# SparkFun_Venus_GPS_SMA_Connector.net
KiCad netlist of a schematic drawn in EAGLE
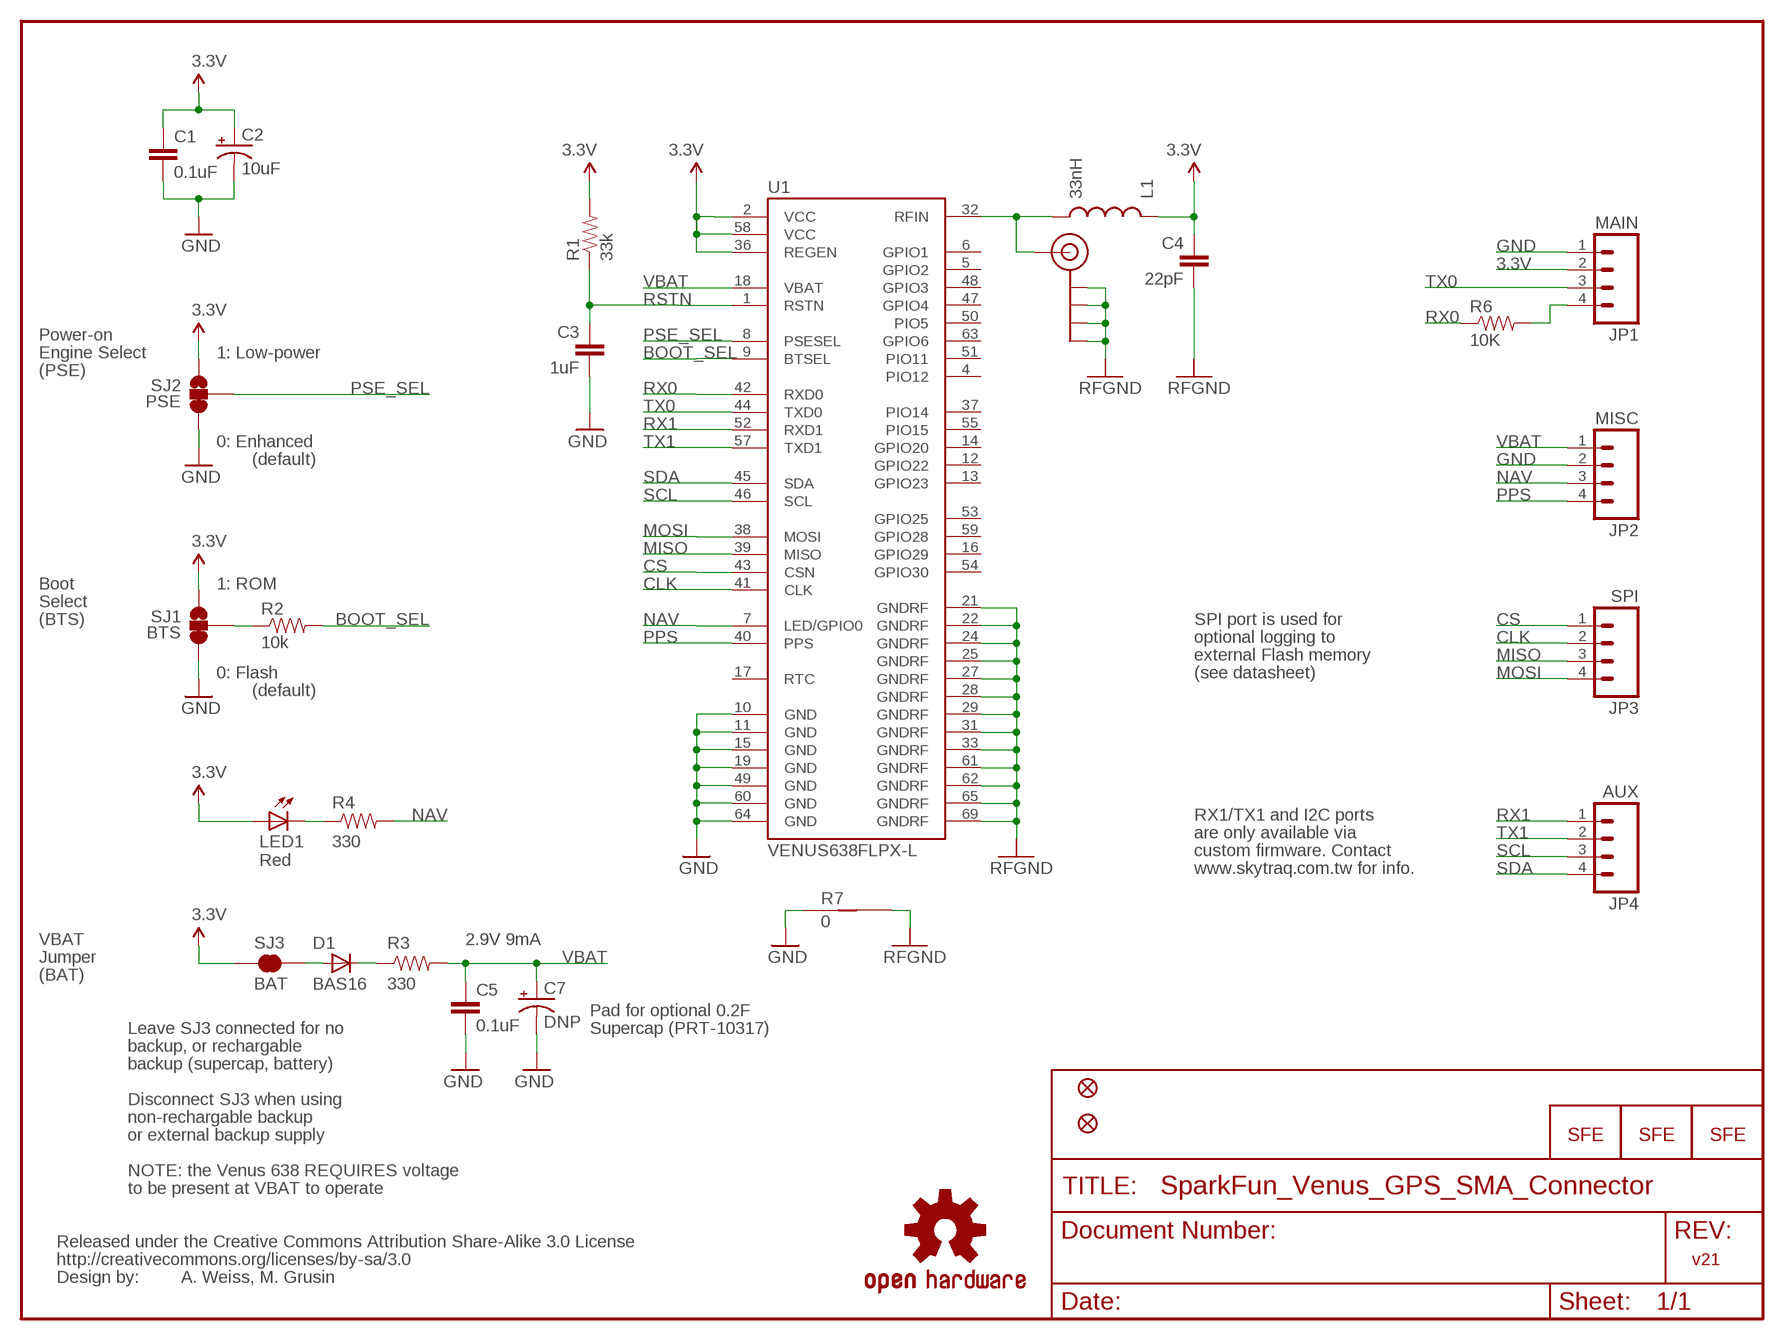
[diagram p0: schematic, sheet 1]

(export (version "E")
  (design (tool "Eeschema 10.0.6"))
  (components
    (comp (ref "C1")
      (value "0.1uF")
      (footprint "eagle-import:0402-CAP")
      (libsource (lib "eagle-import") (part "CAP0402-CAP"))
    )
    (comp (ref "C2")
      (value "10uF")
      (footprint "eagle-import:EIA3216")
      (libsource (lib "eagle-import") (part "CAP_POL1206"))
    )
    (comp (ref "C3")
      (value "1uF")
      (footprint "eagle-import:0402-CAP")
      (libsource (lib "eagle-import") (part "CAP0402-CAP"))
    )
    (comp (ref "C4")
      (value "22pF")
      (footprint "eagle-import:0402-CAP")
      (libsource (lib "eagle-import") (part "CAP0402-CAP"))
    )
    (comp (ref "C5")
      (value "0.1uF")
      (footprint "eagle-import:0402-CAP")
      (libsource (lib "eagle-import") (part "CAP0402-CAP"))
    )
    (comp (ref "C7")
      (value "DNP")
      (footprint "eagle-import:EN_J2")
      (libsource (lib "eagle-import") (part "CAP_POLEN_J2"))
    )
    (comp (ref "D1")
      (value "BAS16")
      (footprint "eagle-import:SOD-323")
      (libsource (lib "eagle-import") (part "DIODESOD"))
    )
    (comp (ref "JP1")
      (value "MAIN")
      (footprint "eagle-import:1X04")
      (libsource (lib "eagle-import") (part "M04PTH"))
    )
    (comp (ref "JP2")
      (value "MISC")
      (footprint "eagle-import:1X04")
      (libsource (lib "eagle-import") (part "M04PTH"))
    )
    (comp (ref "JP3")
      (value "SPI")
      (footprint "eagle-import:1X04")
      (libsource (lib "eagle-import") (part "M04PTH"))
    )
    (comp (ref "JP4")
      (value "AUX")
      (footprint "eagle-import:1X04")
      (libsource (lib "eagle-import") (part "M04PTH"))
    )
    (comp (ref "JP5")
      (value "SMA_EDGE")
      (footprint "eagle-import:SMA-EDGE")
      (libsource (lib "eagle-import") (part "SMA_EDGE"))
    )
    (comp (ref "JP6")
      (value "FIDUCIALUFIDUCIAL")
      (footprint "eagle-import:MICRO-FIDUCIAL")
      (libsource (lib "eagle-import") (part "FIDUCIALUFIDUCIAL"))
    )
    (comp (ref "JP7")
      (value "FIDUCIALUFIDUCIAL")
      (footprint "eagle-import:MICRO-FIDUCIAL")
      (libsource (lib "eagle-import") (part "FIDUCIALUFIDUCIAL"))
    )
    (comp (ref "L1")
      (value "33nH")
      (footprint "eagle-import:C0402")
      (libsource (lib "eagle-import") (part "INDUCTOR0402"))
    )
    (comp (ref "LED1")
      (value "Red")
      (footprint "eagle-import:LED-0603")
      (libsource (lib "eagle-import") (part "LED0603"))
    )
    (comp (ref "LOGO1")
      (value "LOGO-SFESK")
      (footprint "eagle-import:SFE-LOGO-FLAME")
      (libsource (lib "eagle-import") (part "LOGO-SFESK"))
    )
    (comp (ref "LOGO2")
      (value "LOGO-SFESK")
      (footprint "eagle-import:SFE-LOGO-FLAME")
      (libsource (lib "eagle-import") (part "LOGO-SFESK"))
    )
    (comp (ref "LOGO3")
      (value "LOGO-SFENW2")
      (footprint "eagle-import:SFE-NEW-WEB")
      (libsource (lib "eagle-import") (part "LOGO-SFENW2"))
    )
    (comp (ref "R1")
      (value "33k")
      (footprint "eagle-import:0402-RES")
      (libsource (lib "eagle-import") (part "RESISTOR0402-RES"))
    )
    (comp (ref "R2")
      (value "10k")
      (footprint "eagle-import:0402-RES")
      (libsource (lib "eagle-import") (part "RESISTOR0402-RES"))
    )
    (comp (ref "R3")
      (value "330")
      (footprint "eagle-import:0402-RES")
      (libsource (lib "eagle-import") (part "RESISTOR0402-RES"))
    )
    (comp (ref "R4")
      (value "330")
      (footprint "eagle-import:0402-RES")
      (libsource (lib "eagle-import") (part "RESISTOR0402-RES"))
    )
    (comp (ref "R6")
      (value "10K")
      (footprint "eagle-import:0402-RES")
      (libsource (lib "eagle-import") (part "RESISTOR0402-RES"))
    )
    (comp (ref "R7")
      (value "0")
      (footprint "eagle-import:GND-JUMP")
      (libsource (lib "eagle-import") (part "GND-JUMP"))
    )
    (comp (ref "SJ1")
      (value "BTS")
      (footprint "eagle-import:SJ_3_PASTE2&3")
      (libsource (lib "eagle-import") (part "SOLDERJUMPER_2WAYPASTE2&3"))
    )
    (comp (ref "SJ2")
      (value "PSE")
      (footprint "eagle-import:SJ_3_PASTE2&3")
      (libsource (lib "eagle-import") (part "SOLDERJUMPER_2WAYPASTE2&3"))
    )
    (comp (ref "SJ3")
      (value "BAT")
      (footprint "eagle-import:SJ_2S")
      (libsource (lib "eagle-import") (part "SOLDERJUMPERNC"))
    )
    (comp (ref "U$4")
      (value "OSHW-LOGOS")
      (footprint "eagle-import:OSHW-LOGO-S")
      (libsource (lib "eagle-import") (part "OSHW-LOGOS"))
    )
    (comp (ref "U$5")
      (value "CREATIVE_COMMONS")
      (footprint "eagle-import:CREATIVE_COMMONS")
      (libsource (lib "eagle-import") (part "CREATIVE_COMMONS"))
    )
    (comp (ref "U1")
      (value "VENUS638FLPX-L")
      (footprint "eagle-import:VENUS638FLPX")
      (libsource (lib "eagle-import") (part "VENUS638FLPX-L"))
    )
  )
  (nets
    (net (code "1") (name "/BOOT_SEL") (class "Default")
      (node (ref "R2") (pin "2") (pinfunction "2_2") (pintype "passive"))
      (node (ref "U1") (pin "9") (pinfunction "BTSEL_9") (pintype "bidirectional"))
    )
    (net (code "2") (name "/CLK") (class "Default")
      (node (ref "JP3") (pin "2") (pinfunction "2_2") (pintype "passive"))
      (node (ref "U1") (pin "41") (pinfunction "CLK_41") (pintype "bidirectional"))
    )
    (net (code "3") (name "/CS") (class "Default")
      (node (ref "JP3") (pin "1") (pinfunction "1_1") (pintype "passive"))
      (node (ref "U1") (pin "43") (pinfunction "CSN_43") (pintype "bidirectional"))
    )
    (net (code "4") (name "/MISO") (class "Default")
      (node (ref "JP3") (pin "3") (pinfunction "3_3") (pintype "passive"))
      (node (ref "U1") (pin "39") (pinfunction "MISO_39") (pintype "bidirectional"))
    )
    (net (code "5") (name "/MOSI") (class "Default")
      (node (ref "JP3") (pin "4") (pinfunction "4_4") (pintype "passive"))
      (node (ref "U1") (pin "38") (pinfunction "MOSI_38") (pintype "bidirectional"))
    )
    (net (code "6") (name "/NAV") (class "Default")
      (node (ref "JP2") (pin "3") (pinfunction "3_3") (pintype "passive"))
      (node (ref "R4") (pin "2") (pinfunction "2_2") (pintype "passive"))
      (node (ref "U1") (pin "7") (pinfunction "LED/GPIO0_7") (pintype "bidirectional"))
    )
    (net (code "7") (name "/PPS") (class "Default")
      (node (ref "JP2") (pin "4") (pinfunction "4_4") (pintype "passive"))
      (node (ref "U1") (pin "40") (pinfunction "PPS_40") (pintype "bidirectional"))
    )
    (net (code "8") (name "/PSE_SEL") (class "Default")
      (node (ref "SJ2") (pin "2") (pinfunction "2_2") (pintype "passive"))
      (node (ref "U1") (pin "8") (pinfunction "PSESEL_8") (pintype "bidirectional"))
    )
    (net (code "9") (name "/RFGND") (class "Default")
      (node (ref "C4") (pin "2") (pinfunction "2_2") (pintype "passive"))
      (node (ref "JP5") (pin "GND@0") (pinfunction "GND_GND@0") (pintype "bidirectional"))
      (node (ref "JP5") (pin "GND@1") (pinfunction "GND_GND@1") (pintype "bidirectional"))
      (node (ref "JP5") (pin "GND@2") (pinfunction "GND_GND@2") (pintype "bidirectional"))
      (node (ref "JP5") (pin "GND@3") (pinfunction "GND_GND@3") (pintype "bidirectional"))
      (node (ref "R7") (pin "2") (pinfunction "2_2") (pintype "bidirectional"))
      (node (ref "U1") (pin "21") (pinfunction "GNDRF_21") (pintype "bidirectional"))
      (node (ref "U1") (pin "22") (pinfunction "GNDRF_22") (pintype "bidirectional"))
      (node (ref "U1") (pin "24") (pinfunction "GNDRF_24") (pintype "bidirectional"))
      (node (ref "U1") (pin "25") (pinfunction "GNDRF_25") (pintype "bidirectional"))
      (node (ref "U1") (pin "27") (pinfunction "GNDRF_27") (pintype "bidirectional"))
      (node (ref "U1") (pin "28") (pinfunction "GNDRF_28") (pintype "bidirectional"))
      (node (ref "U1") (pin "29") (pinfunction "GNDRF_29") (pintype "bidirectional"))
      (node (ref "U1") (pin "31") (pinfunction "GNDRF_31") (pintype "bidirectional"))
      (node (ref "U1") (pin "33") (pinfunction "GNDRF_33") (pintype "bidirectional"))
      (node (ref "U1") (pin "61") (pinfunction "GNDRF_61") (pintype "bidirectional"))
      (node (ref "U1") (pin "62") (pinfunction "GNDRF_62") (pintype "bidirectional"))
      (node (ref "U1") (pin "65") (pinfunction "GNDRF_65") (pintype "bidirectional"))
      (node (ref "U1") (pin "69") (pinfunction "GNDRF_69") (pintype "bidirectional"))
    )
    (net (code "10") (name "/RSTN") (class "Default")
      (node (ref "C3") (pin "1") (pinfunction "1_1") (pintype "passive"))
      (node (ref "R1") (pin "1") (pinfunction "1_1") (pintype "passive"))
      (node (ref "U1") (pin "1") (pinfunction "RSTN_1") (pintype "bidirectional"))
    )
    (net (code "11") (name "/RX0") (class "Default")
      (node (ref "R6") (pin "1") (pinfunction "1_1") (pintype "passive"))
      (node (ref "U1") (pin "42") (pinfunction "RXD0_42") (pintype "bidirectional"))
    )
    (net (code "12") (name "/RX1") (class "Default")
      (node (ref "JP4") (pin "1") (pinfunction "1_1") (pintype "passive"))
      (node (ref "U1") (pin "52") (pinfunction "RXD1_52") (pintype "bidirectional"))
    )
    (net (code "13") (name "/SCL") (class "Default")
      (node (ref "JP4") (pin "3") (pinfunction "3_3") (pintype "passive"))
      (node (ref "U1") (pin "46") (pinfunction "SCL_46") (pintype "bidirectional"))
    )
    (net (code "14") (name "/SDA") (class "Default")
      (node (ref "JP4") (pin "4") (pinfunction "4_4") (pintype "passive"))
      (node (ref "U1") (pin "45") (pinfunction "SDA_45") (pintype "bidirectional"))
    )
    (net (code "15") (name "/TX0") (class "Default")
      (node (ref "JP1") (pin "3") (pinfunction "3_3") (pintype "passive"))
      (node (ref "U1") (pin "44") (pinfunction "TXD0_44") (pintype "bidirectional"))
    )
    (net (code "16") (name "/TX1") (class "Default")
      (node (ref "JP4") (pin "2") (pinfunction "2_2") (pintype "passive"))
      (node (ref "U1") (pin "57") (pinfunction "TXD1_57") (pintype "bidirectional"))
    )
    (net (code "17") (name "/VBAT") (class "Default")
      (node (ref "C5") (pin "1") (pinfunction "1_1") (pintype "passive"))
      (node (ref "C7") (pin "+") (pinfunction "+_+") (pintype "passive"))
      (node (ref "JP2") (pin "1") (pinfunction "1_1") (pintype "passive"))
      (node (ref "R3") (pin "2") (pinfunction "2_2") (pintype "passive"))
      (node (ref "U1") (pin "18") (pinfunction "VBAT_18") (pintype "bidirectional"))
    )
    (net (code "18") (name "3.3V") (class "Default")
      (node (ref "C1") (pin "1") (pinfunction "1_1") (pintype "passive"))
      (node (ref "C2") (pin "A") (pinfunction "+_A") (pintype "passive"))
      (node (ref "C4") (pin "1") (pinfunction "1_1") (pintype "passive"))
      (node (ref "JP1") (pin "2") (pinfunction "2_2") (pintype "passive"))
      (node (ref "L1") (pin "1") (pinfunction "1_1") (pintype "passive"))
      (node (ref "LED1") (pin "A") (pinfunction "A_A") (pintype "passive"))
      (node (ref "R1") (pin "2") (pinfunction "2_2") (pintype "passive"))
      (node (ref "SJ1") (pin "1") (pinfunction "1_1") (pintype "passive"))
      (node (ref "SJ2") (pin "1") (pinfunction "1_1") (pintype "passive"))
      (node (ref "SJ3") (pin "1") (pinfunction "1_1") (pintype "passive"))
      (node (ref "U1") (pin "2") (pinfunction "VCC_2") (pintype "bidirectional"))
      (node (ref "U1") (pin "36") (pinfunction "REGEN_36") (pintype "bidirectional"))
      (node (ref "U1") (pin "58") (pinfunction "VCC_58") (pintype "bidirectional"))
    )
    (net (code "19") (name "GND") (class "Default")
      (node (ref "C1") (pin "2") (pinfunction "2_2") (pintype "passive"))
      (node (ref "C2") (pin "C") (pinfunction "-_C") (pintype "passive"))
      (node (ref "C3") (pin "2") (pinfunction "2_2") (pintype "passive"))
      (node (ref "C5") (pin "2") (pinfunction "2_2") (pintype "passive"))
      (node (ref "C7") (pin "-") (pinfunction "-_-") (pintype "passive"))
      (node (ref "JP1") (pin "1") (pinfunction "1_1") (pintype "passive"))
      (node (ref "JP2") (pin "2") (pinfunction "2_2") (pintype "passive"))
      (node (ref "R7") (pin "1") (pinfunction "1_1") (pintype "bidirectional"))
      (node (ref "SJ1") (pin "3") (pinfunction "3_3") (pintype "passive"))
      (node (ref "SJ2") (pin "3") (pinfunction "3_3") (pintype "passive"))
      (node (ref "U1") (pin "10") (pinfunction "GND_10") (pintype "bidirectional"))
      (node (ref "U1") (pin "11") (pinfunction "GND_11") (pintype "bidirectional"))
      (node (ref "U1") (pin "15") (pinfunction "GND_15") (pintype "bidirectional"))
      (node (ref "U1") (pin "19") (pinfunction "GND_19") (pintype "bidirectional"))
      (node (ref "U1") (pin "49") (pinfunction "GND_49") (pintype "bidirectional"))
      (node (ref "U1") (pin "60") (pinfunction "GND_60") (pintype "bidirectional"))
      (node (ref "U1") (pin "64") (pinfunction "GND_64") (pintype "bidirectional"))
    )
    (net (code "20") (name "Net-(D1-A)") (class "Default")
      (node (ref "D1") (pin "2") (pinfunction "A_2") (pintype "passive"))
      (node (ref "SJ3") (pin "2") (pinfunction "2_2") (pintype "passive"))
    )
    (net (code "21") (name "Net-(D1-C)") (class "Default")
      (node (ref "D1") (pin "1") (pinfunction "C_1") (pintype "passive"))
      (node (ref "R3") (pin "1") (pinfunction "1_1") (pintype "passive"))
    )
    (net (code "22") (name "Net-(JP1-Pad4)") (class "Default")
      (node (ref "JP1") (pin "4") (pinfunction "4_4") (pintype "passive"))
      (node (ref "R6") (pin "2") (pinfunction "2_2") (pintype "passive"))
    )
    (net (code "23") (name "Net-(JP5-SIGNAL)") (class "Default")
      (node (ref "JP5") (pin "SIG") (pinfunction "SIGNAL_SIG") (pintype "bidirectional"))
      (node (ref "L1") (pin "2") (pinfunction "2_2") (pintype "passive"))
      (node (ref "U1") (pin "32") (pinfunction "RFIN_32") (pintype "bidirectional"))
    )
    (net (code "24") (name "Net-(LED1-PadC)") (class "Default")
      (node (ref "LED1") (pin "C") (pinfunction "C_C") (pintype "passive"))
      (node (ref "R4") (pin "1") (pinfunction "1_1") (pintype "passive"))
    )
    (net (code "25") (name "Net-(R2-Pad1)") (class "Default")
      (node (ref "R2") (pin "1") (pinfunction "1_1") (pintype "passive"))
      (node (ref "SJ1") (pin "2") (pinfunction "2_2") (pintype "passive"))
    )
    (net (code "26") (name "unconnected-(U1-GPIO1-Pad6)") (class "Default")
      (node (ref "U1") (pin "6") (pinfunction "GPIO1_6") (pintype "bidirectional"))
    )
    (net (code "27") (name "unconnected-(U1-GPIO2-Pad5)") (class "Default")
      (node (ref "U1") (pin "5") (pinfunction "GPIO2_5") (pintype "bidirectional"))
    )
    (net (code "28") (name "unconnected-(U1-GPIO3-Pad48)") (class "Default")
      (node (ref "U1") (pin "48") (pinfunction "GPIO3_48") (pintype "bidirectional"))
    )
    (net (code "29") (name "unconnected-(U1-GPIO4-Pad47)") (class "Default")
      (node (ref "U1") (pin "47") (pinfunction "GPIO4_47") (pintype "bidirectional"))
    )
    (net (code "30") (name "unconnected-(U1-GPIO6-Pad63)") (class "Default")
      (node (ref "U1") (pin "63") (pinfunction "GPIO6_63") (pintype "bidirectional"))
    )
    (net (code "31") (name "unconnected-(U1-GPIO20-Pad14)") (class "Default")
      (node (ref "U1") (pin "14") (pinfunction "GPIO20_14") (pintype "bidirectional"))
    )
    (net (code "32") (name "unconnected-(U1-GPIO22-Pad12)") (class "Default")
      (node (ref "U1") (pin "12") (pinfunction "GPIO22_12") (pintype "bidirectional"))
    )
    (net (code "33") (name "unconnected-(U1-GPIO23-Pad13)") (class "Default")
      (node (ref "U1") (pin "13") (pinfunction "GPIO23_13") (pintype "bidirectional"))
    )
    (net (code "34") (name "unconnected-(U1-GPIO25-Pad53)") (class "Default")
      (node (ref "U1") (pin "53") (pinfunction "GPIO25_53") (pintype "bidirectional"))
    )
    (net (code "35") (name "unconnected-(U1-GPIO28-Pad59)") (class "Default")
      (node (ref "U1") (pin "59") (pinfunction "GPIO28_59") (pintype "bidirectional"))
    )
    (net (code "36") (name "unconnected-(U1-GPIO29-Pad16)") (class "Default")
      (node (ref "U1") (pin "16") (pinfunction "GPIO29_16") (pintype "bidirectional"))
    )
    (net (code "37") (name "unconnected-(U1-GPIO30-Pad54)") (class "Default")
      (node (ref "U1") (pin "54") (pinfunction "GPIO30_54") (pintype "bidirectional"))
    )
    (net (code "38") (name "unconnected-(U1-PIO5-Pad50)") (class "Default")
      (node (ref "U1") (pin "50") (pinfunction "PIO5_50") (pintype "bidirectional"))
    )
    (net (code "39") (name "unconnected-(U1-PIO11-Pad51)") (class "Default")
      (node (ref "U1") (pin "51") (pinfunction "PIO11_51") (pintype "bidirectional"))
    )
    (net (code "40") (name "unconnected-(U1-PIO12-Pad4)") (class "Default")
      (node (ref "U1") (pin "4") (pinfunction "PIO12_4") (pintype "bidirectional"))
    )
    (net (code "41") (name "unconnected-(U1-PIO14-Pad37)") (class "Default")
      (node (ref "U1") (pin "37") (pinfunction "PIO14_37") (pintype "bidirectional"))
    )
    (net (code "42") (name "unconnected-(U1-PIO15-Pad55)") (class "Default")
      (node (ref "U1") (pin "55") (pinfunction "PIO15_55") (pintype "bidirectional"))
    )
    (net (code "43") (name "unconnected-(U1-RTC-Pad17)") (class "Default")
      (node (ref "U1") (pin "17") (pinfunction "RTC_17") (pintype "bidirectional"))
    )
  )
)
